# BatteryMonitorSchematic.net
KiCad netlist of a schematic drawn in Altium Designer
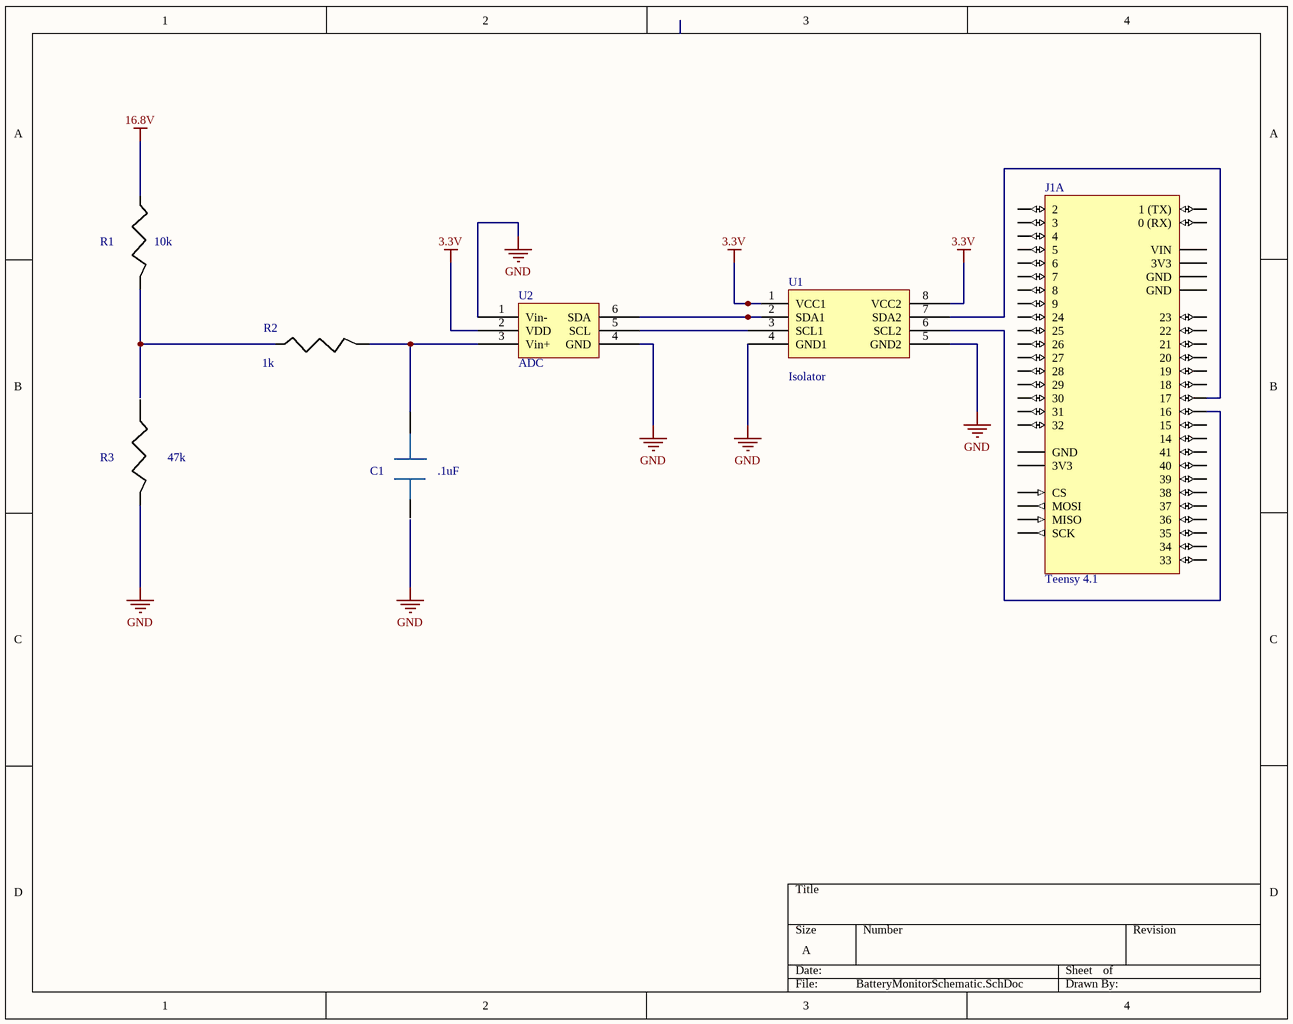
[diagram p0: BatteryMonitorSchematic.SchDoc]

(export (version "E")
  (design (tool "Eeschema 10.0.6"))
  (components
    (comp (ref "C1")
      (value "UCB1V0R1MCL1GS")
      (description "Aluminum Electrolytic Capacitors - SMD 32volts 0.1uF 105c 4x7")
      (fields (field (name "MANUFACTURER") "Nichicon") (field (name "TOLERANCE") "20%"))
      (libsource (lib "BatteryMonitorLib") (part "UCB1V0R1MCL1GS"))
    )
    (comp (ref "J1")
      (value "Teensy 4.1")
      (footprint "Teensy4.1")
      (libsource (lib "Teensy4.1") (part "Teensy4.1"))
    )
    (comp (ref "R1")
      (value "~")
      (fields
        (field (name "MANUFACTURER") "KOA Speer")
        (field (name "MANUFACTURER PART NUMBER") "RN73R2ETTD1001F25")
        (field (name "SUPPLIER PART NUMBER 1") "10k")
      )
      (libsource (lib "BatteryMonitorLib") (part "RN73R2ETTD1001F25"))
    )
    (comp (ref "R2")
      (value "1k Ohm RN73R2ETTD1001F25")
      (fields
        (field (name "MANUFACTURER") "KOA Speer")
        (field (name "MANUFACTURER PART NUMBER") "RN73R2ETTD1001F25")
      )
      (libsource (lib "BatteryMonitorLib") (part "RN73R2ETTD1001F25"))
    )
    (comp (ref "R3")
      (value "47k")
      (description "Resistor Thick Film 47kOhm 5% 2-Pin Surface Mount 3502 T/R")
      (fields
        (field (name "MANUFACTURER") "TE Connectivity")
        (field (name "MANUFACTURER PART NUMBER") "350247KJT")
      )
      (libsource (lib "BatteryMonitorLib") (part "350247KJT (2)"))
    )
    (comp (ref "U1")
      (value "ISO1540DR")
      (description "TEXAS INSTRUMENTS - ISO1540DR - DIGITAL ISOLATOR, 2-CH, 1MBPS, SOIC-8")
      (fields (field (name "MANUFACTURER") "Texas Instruments"))
      (libsource (lib "BatteryMonitorLib") (part "ISO1540DR"))
    )
    (comp (ref "U2")
      (value "ADC")
      (description "IC ADC 12BIT I2C INTRFC SOT23-6")
      (fields
        (field (name "MANUFACTURER") "Texas Instruments")
        (field (name "MANUFACTURER PART NUMBER") "ADS1000A0IDBVT")
      )
      (libsource (lib "BatteryMonitorLib") (part "ADS1000A0IDBVT"))
    )
  )
  (nets
    (net (code "1") (name "3.3V") (class "Default")
      (node (ref "U1") (pin "1") (pinfunction "VCC1_1") (pintype "passive"))
      (node (ref "U1") (pin "8") (pinfunction "VCC2_8") (pintype "passive"))
      (node (ref "U2") (pin "2") (pinfunction "VDD_2") (pintype "passive"))
    )
    (net (code "3") (name "GND") (class "Default")
      (node (ref "U1") (pin "4") (pinfunction "GND1_4") (pintype "passive"))
      (node (ref "U1") (pin "5") (pinfunction "GND2_5") (pintype "passive"))
      (node (ref "U2") (pin "1") (pinfunction "Vin-_1") (pintype "passive"))
      (node (ref "U2") (pin "4") (pinfunction "GND_4") (pintype "passive"))
    )
    (net (code "4") (name "Net-(J1A-16)") (class "Default")
      (node (ref "J1") (pin "38") (pinfunction "16_38") (pintype "bidirectional"))
      (node (ref "U1") (pin "6") (pinfunction "SCL2_6") (pintype "passive"))
    )
    (net (code "5") (name "Net-(J1A-17)") (class "Default")
      (node (ref "J1") (pin "39") (pinfunction "17_39") (pintype "bidirectional"))
      (node (ref "U1") (pin "7") (pinfunction "SDA2_7") (pintype "passive"))
    )
    (net (code "6") (name "Net-(U1-SCL1)") (class "Default")
      (node (ref "U1") (pin "3") (pinfunction "SCL1_3") (pintype "passive"))
      (node (ref "U2") (pin "5") (pinfunction "SCL_5") (pintype "passive"))
    )
    (net (code "7") (name "Net-(U1-SDA1)") (class "Default")
      (node (ref "U1") (pin "2") (pinfunction "SDA1_2") (pintype "passive"))
      (node (ref "U2") (pin "6") (pinfunction "SDA_6") (pintype "passive"))
    )
    (net (code "8") (name "unconnected-(J1A-0_(RX)-Pad2)") (class "Default")
      (node (ref "J1") (pin "2") (pinfunction "0_(RX)_2") (pintype "bidirectional"))
    )
    (net (code "9") (name "unconnected-(J1A-1_(TX)-Pad3)") (class "Default")
      (node (ref "J1") (pin "3") (pinfunction "1_(TX)_3") (pintype "bidirectional"))
    )
    (net (code "10") (name "unconnected-(J1A-2-Pad4)") (class "Default")
      (node (ref "J1") (pin "4") (pinfunction "2_4") (pintype "bidirectional"))
    )
    (net (code "11") (name "unconnected-(J1A-3-Pad5)") (class "Default")
      (node (ref "J1") (pin "5") (pinfunction "3_5") (pintype "bidirectional"))
    )
    (net (code "12") (name "unconnected-(J1A-3V3-Pad15)") (class "Default")
      (node (ref "J1") (pin "15") (pinfunction "3V3_15") (pintype "power_in"))
    )
    (net (code "13") (name "unconnected-(J1A-3V3-Pad46)") (class "Default")
      (node (ref "J1") (pin "46") (pinfunction "3V3_46") (pintype "power_in"))
    )
    (net (code "14") (name "unconnected-(J1A-4-Pad6)") (class "Default")
      (node (ref "J1") (pin "6") (pinfunction "4_6") (pintype "bidirectional"))
    )
    (net (code "15") (name "unconnected-(J1A-5-Pad7)") (class "Default")
      (node (ref "J1") (pin "7") (pinfunction "5_7") (pintype "bidirectional"))
    )
    (net (code "16") (name "unconnected-(J1A-6-Pad8)") (class "Default")
      (node (ref "J1") (pin "8") (pinfunction "6_8") (pintype "bidirectional"))
    )
    (net (code "17") (name "unconnected-(J1A-7-Pad9)") (class "Default")
      (node (ref "J1") (pin "9") (pinfunction "7_9") (pintype "bidirectional"))
    )
    (net (code "18") (name "unconnected-(J1A-8-Pad10)") (class "Default")
      (node (ref "J1") (pin "10") (pinfunction "8_10") (pintype "bidirectional"))
    )
    (net (code "19") (name "unconnected-(J1A-9-Pad11)") (class "Default")
      (node (ref "J1") (pin "11") (pinfunction "9_11") (pintype "bidirectional"))
    )
    (net (code "20") (name "unconnected-(J1A-14-Pad36)") (class "Default")
      (node (ref "J1") (pin "36") (pinfunction "14_36") (pintype "bidirectional"))
    )
    (net (code "21") (name "unconnected-(J1A-15-Pad37)") (class "Default")
      (node (ref "J1") (pin "37") (pinfunction "15_37") (pintype "bidirectional"))
    )
    (net (code "22") (name "unconnected-(J1A-18-Pad40)") (class "Default")
      (node (ref "J1") (pin "40") (pinfunction "18_40") (pintype "bidirectional"))
    )
    (net (code "23") (name "unconnected-(J1A-19-Pad41)") (class "Default")
      (node (ref "J1") (pin "41") (pinfunction "19_41") (pintype "bidirectional"))
    )
    (net (code "24") (name "unconnected-(J1A-20-Pad42)") (class "Default")
      (node (ref "J1") (pin "42") (pinfunction "20_42") (pintype "bidirectional"))
    )
    (net (code "25") (name "unconnected-(J1A-21-Pad43)") (class "Default")
      (node (ref "J1") (pin "43") (pinfunction "21_43") (pintype "bidirectional"))
    )
    (net (code "26") (name "unconnected-(J1A-22-Pad44)") (class "Default")
      (node (ref "J1") (pin "44") (pinfunction "22_44") (pintype "bidirectional"))
    )
    (net (code "27") (name "unconnected-(J1A-23-Pad45)") (class "Default")
      (node (ref "J1") (pin "45") (pinfunction "23_45") (pintype "bidirectional"))
    )
    (net (code "28") (name "unconnected-(J1A-24-Pad16)") (class "Default")
      (node (ref "J1") (pin "16") (pinfunction "24_16") (pintype "bidirectional"))
    )
    (net (code "29") (name "unconnected-(J1A-25-Pad17)") (class "Default")
      (node (ref "J1") (pin "17") (pinfunction "25_17") (pintype "bidirectional"))
    )
    (net (code "30") (name "unconnected-(J1A-26-Pad18)") (class "Default")
      (node (ref "J1") (pin "18") (pinfunction "26_18") (pintype "bidirectional"))
    )
    (net (code "31") (name "unconnected-(J1A-27-Pad19)") (class "Default")
      (node (ref "J1") (pin "19") (pinfunction "27_19") (pintype "bidirectional"))
    )
    (net (code "32") (name "unconnected-(J1A-28-Pad20)") (class "Default")
      (node (ref "J1") (pin "20") (pinfunction "28_20") (pintype "bidirectional"))
    )
    (net (code "33") (name "unconnected-(J1A-29-Pad21)") (class "Default")
      (node (ref "J1") (pin "21") (pinfunction "29_21") (pintype "bidirectional"))
    )
    (net (code "34") (name "unconnected-(J1A-30-Pad22)") (class "Default")
      (node (ref "J1") (pin "22") (pinfunction "30_22") (pintype "bidirectional"))
    )
    (net (code "35") (name "unconnected-(J1A-31-Pad23)") (class "Default")
      (node (ref "J1") (pin "23") (pinfunction "31_23") (pintype "bidirectional"))
    )
    (net (code "36") (name "unconnected-(J1A-32-Pad24)") (class "Default")
      (node (ref "J1") (pin "24") (pinfunction "32_24") (pintype "bidirectional"))
    )
    (net (code "37") (name "unconnected-(J1A-33-Pad25)") (class "Default")
      (node (ref "J1") (pin "25") (pinfunction "33_25") (pintype "bidirectional"))
    )
    (net (code "38") (name "unconnected-(J1A-34-Pad26)") (class "Default")
      (node (ref "J1") (pin "26") (pinfunction "34_26") (pintype "bidirectional"))
    )
    (net (code "39") (name "unconnected-(J1A-35-Pad27)") (class "Default")
      (node (ref "J1") (pin "27") (pinfunction "35_27") (pintype "bidirectional"))
    )
    (net (code "40") (name "unconnected-(J1A-36-Pad28)") (class "Default")
      (node (ref "J1") (pin "28") (pinfunction "36_28") (pintype "bidirectional"))
    )
    (net (code "41") (name "unconnected-(J1A-37-Pad29)") (class "Default")
      (node (ref "J1") (pin "29") (pinfunction "37_29") (pintype "bidirectional"))
    )
    (net (code "42") (name "unconnected-(J1A-38-Pad30)") (class "Default")
      (node (ref "J1") (pin "30") (pinfunction "38_30") (pintype "bidirectional"))
    )
    (net (code "43") (name "unconnected-(J1A-39-Pad31)") (class "Default")
      (node (ref "J1") (pin "31") (pinfunction "39_31") (pintype "bidirectional"))
    )
    (net (code "44") (name "unconnected-(J1A-40-Pad32)") (class "Default")
      (node (ref "J1") (pin "32") (pinfunction "40_32") (pintype "bidirectional"))
    )
    (net (code "45") (name "unconnected-(J1A-41-Pad33)") (class "Default")
      (node (ref "J1") (pin "33") (pinfunction "41_33") (pintype "bidirectional"))
    )
    (net (code "46") (name "unconnected-(J1A-CS-Pad12)") (class "Default")
      (node (ref "J1") (pin "12") (pinfunction "CS_12") (pintype "input"))
    )
    (net (code "47") (name "unconnected-(J1A-GND-Pad1)") (class "Default")
      (node (ref "J1") (pin "1") (pinfunction "GND_1") (pintype "power_in"))
    )
    (net (code "48") (name "unconnected-(J1A-GND-Pad34)") (class "Default")
      (node (ref "J1") (pin "34") (pinfunction "GND_34") (pintype "power_in"))
    )
    (net (code "49") (name "unconnected-(J1A-GND-Pad47)") (class "Default")
      (node (ref "J1") (pin "47") (pinfunction "GND_47") (pintype "power_in"))
    )
    (net (code "50") (name "unconnected-(J1A-MISO-Pad14)") (class "Default")
      (node (ref "J1") (pin "14") (pinfunction "MISO_14") (pintype "input"))
    )
    (net (code "51") (name "unconnected-(J1A-MOSI-Pad13)") (class "Default")
      (node (ref "J1") (pin "13") (pinfunction "MOSI_13") (pintype "output"))
    )
    (net (code "52") (name "unconnected-(J1A-SCK-Pad35)") (class "Default")
      (node (ref "J1") (pin "35") (pinfunction "SCK_35") (pintype "output"))
    )
    (net (code "53") (name "unconnected-(J1A-VIN-Pad48)") (class "Default")
      (node (ref "J1") (pin "48") (pinfunction "VIN_48") (pintype "power_in"))
    )
    (net (code "54") (name "unconnected-(U2-Vin+-Pad3)") (class "Default")
      (node (ref "U2") (pin "3") (pinfunction "Vin+_3") (pintype "passive"))
    )
  )
)
